# schema.net
KiCad netlist of a schematic drawn in EAGLE
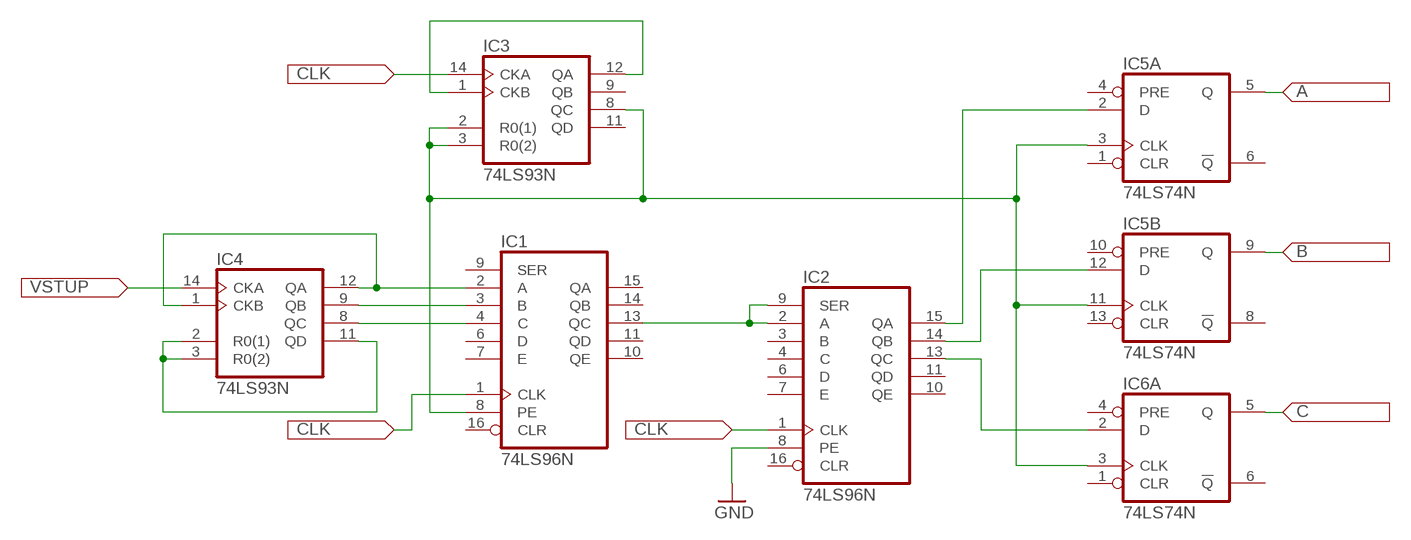
[diagram p0: schematic, sheet 1]

(export (version "E")
  (design (tool "Eeschema 10.0.6"))
  (components
    (comp (ref "IC1")
      (value "74LS96N")
      (footprint "eagle-import:DIL16")
      (libsource (lib "eagle-import") (part "7496NLS"))
    )
    (comp (ref "IC2")
      (value "74LS96N")
      (footprint "eagle-import:DIL16")
      (libsource (lib "eagle-import") (part "7496NLS"))
    )
    (comp (ref "IC3")
      (value "74LS93N")
      (footprint "eagle-import:DIL14")
      (libsource (lib "eagle-import") (part "7493NLS"))
    )
    (comp (ref "IC4")
      (value "74LS93N")
      (footprint "eagle-import:DIL14")
      (libsource (lib "eagle-import") (part "7493NLS"))
    )
    (comp (ref "IC5")
      (value "74LS74N")
      (footprint "eagle-import:DIL14")
      (libsource (lib "eagle-import") (part "7474NLS"))
    )
    (comp (ref "IC6")
      (value "74LS74N")
      (footprint "eagle-import:DIL14")
      (libsource (lib "eagle-import") (part "7474NLS"))
    )
  )
  (nets
    (net (code "1") (name "GND") (class "Default")
      (node (ref "IC2") (pin "8") (pinfunction "PE_8") (pintype "input"))
    )
    (net (code "2") (name "Net-(IC1A-A)") (class "Default")
      (node (ref "IC1") (pin "2") (pinfunction "A_2") (pintype "input"))
      (node (ref "IC4") (pin "1") (pinfunction "CKB_1") (pintype "input"))
      (node (ref "IC4") (pin "12") (pinfunction "QA_12") (pintype "output"))
    )
    (net (code "3") (name "Net-(IC1A-B)") (class "Default")
      (node (ref "IC1") (pin "3") (pinfunction "B_3") (pintype "input"))
      (node (ref "IC4") (pin "9") (pinfunction "QB_9") (pintype "output"))
    )
    (net (code "4") (name "Net-(IC1A-C)") (class "Default")
      (node (ref "IC1") (pin "4") (pinfunction "C_4") (pintype "input"))
      (node (ref "IC4") (pin "8") (pinfunction "QC_8") (pintype "output"))
    )
    (net (code "5") (name "Net-(IC1A-PE)") (class "Default")
      (node (ref "IC1") (pin "8") (pinfunction "PE_8") (pintype "input"))
      (node (ref "IC3") (pin "2") (pinfunction "R0(1)_2") (pintype "input"))
      (node (ref "IC3") (pin "3") (pinfunction "R0(2)_3") (pintype "input"))
      (node (ref "IC3") (pin "8") (pinfunction "QC_8") (pintype "output"))
      (node (ref "IC5") (pin "11") (pinfunction "CLK_11") (pintype "input"))
      (node (ref "IC5") (pin "3") (pinfunction "CLK_3") (pintype "input"))
      (node (ref "IC6") (pin "3") (pinfunction "CLK_3") (pintype "input"))
    )
    (net (code "6") (name "Net-(IC1A-QC)") (class "Default")
      (node (ref "IC1") (pin "13") (pinfunction "QC_13") (pintype "output"))
      (node (ref "IC2") (pin "2") (pinfunction "A_2") (pintype "input"))
      (node (ref "IC2") (pin "9") (pinfunction "SER_9") (pintype "input"))
    )
    (net (code "7") (name "Net-(IC2A-QA)") (class "Default")
      (node (ref "IC2") (pin "15") (pinfunction "QA_15") (pintype "output"))
      (node (ref "IC5") (pin "2") (pinfunction "D_2") (pintype "input"))
    )
    (net (code "8") (name "Net-(IC2A-QB)") (class "Default")
      (node (ref "IC2") (pin "14") (pinfunction "QB_14") (pintype "output"))
      (node (ref "IC5") (pin "12") (pinfunction "D_12") (pintype "input"))
    )
    (net (code "9") (name "Net-(IC2A-QC)") (class "Default")
      (node (ref "IC2") (pin "13") (pinfunction "QC_13") (pintype "output"))
      (node (ref "IC6") (pin "2") (pinfunction "D_2") (pintype "input"))
    )
    (net (code "10") (name "Net-(IC3A-CKB)") (class "Default")
      (node (ref "IC3") (pin "1") (pinfunction "CKB_1") (pintype "input"))
      (node (ref "IC3") (pin "12") (pinfunction "QA_12") (pintype "output"))
    )
    (net (code "11") (name "Net-(IC4A-QD)") (class "Default")
      (node (ref "IC4") (pin "11") (pinfunction "QD_11") (pintype "output"))
      (node (ref "IC4") (pin "2") (pinfunction "R0(1)_2") (pintype "input"))
      (node (ref "IC4") (pin "3") (pinfunction "R0(2)_3") (pintype "input"))
    )
    (net (code "12") (name "unconnected-(IC1A-CLK-Pad1)") (class "Default")
      (node (ref "IC1") (pin "1") (pinfunction "CLK_1") (pintype "input"))
    )
    (net (code "13") (name "unconnected-(IC1A-CLR-Pad16)") (class "Default")
      (node (ref "IC1") (pin "16") (pinfunction "CLR_16") (pintype "input"))
    )
    (net (code "14") (name "unconnected-(IC1A-D-Pad6)") (class "Default")
      (node (ref "IC1") (pin "6") (pinfunction "D_6") (pintype "input"))
    )
    (net (code "15") (name "unconnected-(IC1A-E-Pad7)") (class "Default")
      (node (ref "IC1") (pin "7") (pinfunction "E_7") (pintype "input"))
    )
    (net (code "16") (name "unconnected-(IC1A-QA-Pad15)") (class "Default")
      (node (ref "IC1") (pin "15") (pinfunction "QA_15") (pintype "output"))
    )
    (net (code "17") (name "unconnected-(IC1A-QB-Pad14)") (class "Default")
      (node (ref "IC1") (pin "14") (pinfunction "QB_14") (pintype "output"))
    )
    (net (code "18") (name "unconnected-(IC1A-QD-Pad11)") (class "Default")
      (node (ref "IC1") (pin "11") (pinfunction "QD_11") (pintype "output"))
    )
    (net (code "19") (name "unconnected-(IC1A-QE-Pad10)") (class "Default")
      (node (ref "IC1") (pin "10") (pinfunction "QE_10") (pintype "output"))
    )
    (net (code "20") (name "unconnected-(IC1A-SER-Pad9)") (class "Default")
      (node (ref "IC1") (pin "9") (pinfunction "SER_9") (pintype "input"))
    )
    (net (code "21") (name "unconnected-(IC2A-B-Pad3)") (class "Default")
      (node (ref "IC2") (pin "3") (pinfunction "B_3") (pintype "input"))
    )
    (net (code "22") (name "unconnected-(IC2A-C-Pad4)") (class "Default")
      (node (ref "IC2") (pin "4") (pinfunction "C_4") (pintype "input"))
    )
    (net (code "23") (name "unconnected-(IC2A-CLK-Pad1)") (class "Default")
      (node (ref "IC2") (pin "1") (pinfunction "CLK_1") (pintype "input"))
    )
    (net (code "24") (name "unconnected-(IC2A-CLR-Pad16)") (class "Default")
      (node (ref "IC2") (pin "16") (pinfunction "CLR_16") (pintype "input"))
    )
    (net (code "25") (name "unconnected-(IC2A-D-Pad6)") (class "Default")
      (node (ref "IC2") (pin "6") (pinfunction "D_6") (pintype "input"))
    )
    (net (code "26") (name "unconnected-(IC2A-E-Pad7)") (class "Default")
      (node (ref "IC2") (pin "7") (pinfunction "E_7") (pintype "input"))
    )
    (net (code "27") (name "unconnected-(IC2A-QD-Pad11)") (class "Default")
      (node (ref "IC2") (pin "11") (pinfunction "QD_11") (pintype "output"))
    )
    (net (code "28") (name "unconnected-(IC2A-QE-Pad10)") (class "Default")
      (node (ref "IC2") (pin "10") (pinfunction "QE_10") (pintype "output"))
    )
    (net (code "29") (name "unconnected-(IC3A-CKA-Pad14)") (class "Default")
      (node (ref "IC3") (pin "14") (pinfunction "CKA_14") (pintype "input"))
    )
    (net (code "30") (name "unconnected-(IC3A-QB-Pad9)") (class "Default")
      (node (ref "IC3") (pin "9") (pinfunction "QB_9") (pintype "output"))
    )
    (net (code "31") (name "unconnected-(IC3A-QD-Pad11)") (class "Default")
      (node (ref "IC3") (pin "11") (pinfunction "QD_11") (pintype "output"))
    )
    (net (code "32") (name "unconnected-(IC4A-CKA-Pad14)") (class "Default")
      (node (ref "IC4") (pin "14") (pinfunction "CKA_14") (pintype "input"))
    )
    (net (code "33") (name "unconnected-(IC5A-CLR-Pad1)") (class "Default")
      (node (ref "IC5") (pin "1") (pinfunction "CLR_1") (pintype "input"))
    )
    (net (code "34") (name "unconnected-(IC5A-PRE-Pad4)") (class "Default")
      (node (ref "IC5") (pin "4") (pinfunction "PRE_4") (pintype "input"))
    )
    (net (code "35") (name "unconnected-(IC5A-Q-Pad5)") (class "Default")
      (node (ref "IC5") (pin "5") (pinfunction "Q_5") (pintype "output"))
    )
    (net (code "36") (name "unconnected-(IC5A-~{Q}-Pad6)") (class "Default")
      (node (ref "IC5") (pin "6") (pinfunction "~{Q}_6") (pintype "output"))
    )
    (net (code "37") (name "unconnected-(IC5B-CLR-Pad13)") (class "Default")
      (node (ref "IC5") (pin "13") (pinfunction "CLR_13") (pintype "input"))
    )
    (net (code "38") (name "unconnected-(IC5B-PRE-Pad10)") (class "Default")
      (node (ref "IC5") (pin "10") (pinfunction "PRE_10") (pintype "input"))
    )
    (net (code "39") (name "unconnected-(IC5B-Q-Pad9)") (class "Default")
      (node (ref "IC5") (pin "9") (pinfunction "Q_9") (pintype "output"))
    )
    (net (code "40") (name "unconnected-(IC5B-~{Q}-Pad8)") (class "Default")
      (node (ref "IC5") (pin "8") (pinfunction "~{Q}_8") (pintype "output"))
    )
    (net (code "41") (name "unconnected-(IC6A-CLR-Pad1)") (class "Default")
      (node (ref "IC6") (pin "1") (pinfunction "CLR_1") (pintype "input"))
    )
    (net (code "42") (name "unconnected-(IC6A-PRE-Pad4)") (class "Default")
      (node (ref "IC6") (pin "4") (pinfunction "PRE_4") (pintype "input"))
    )
    (net (code "43") (name "unconnected-(IC6A-Q-Pad5)") (class "Default")
      (node (ref "IC6") (pin "5") (pinfunction "Q_5") (pintype "output"))
    )
    (net (code "44") (name "unconnected-(IC6A-~{Q}-Pad6)") (class "Default")
      (node (ref "IC6") (pin "6") (pinfunction "~{Q}_6") (pintype "output"))
    )
  )
)
